# indor.net
KiCad netlist of a schematic drawn in EAGLE
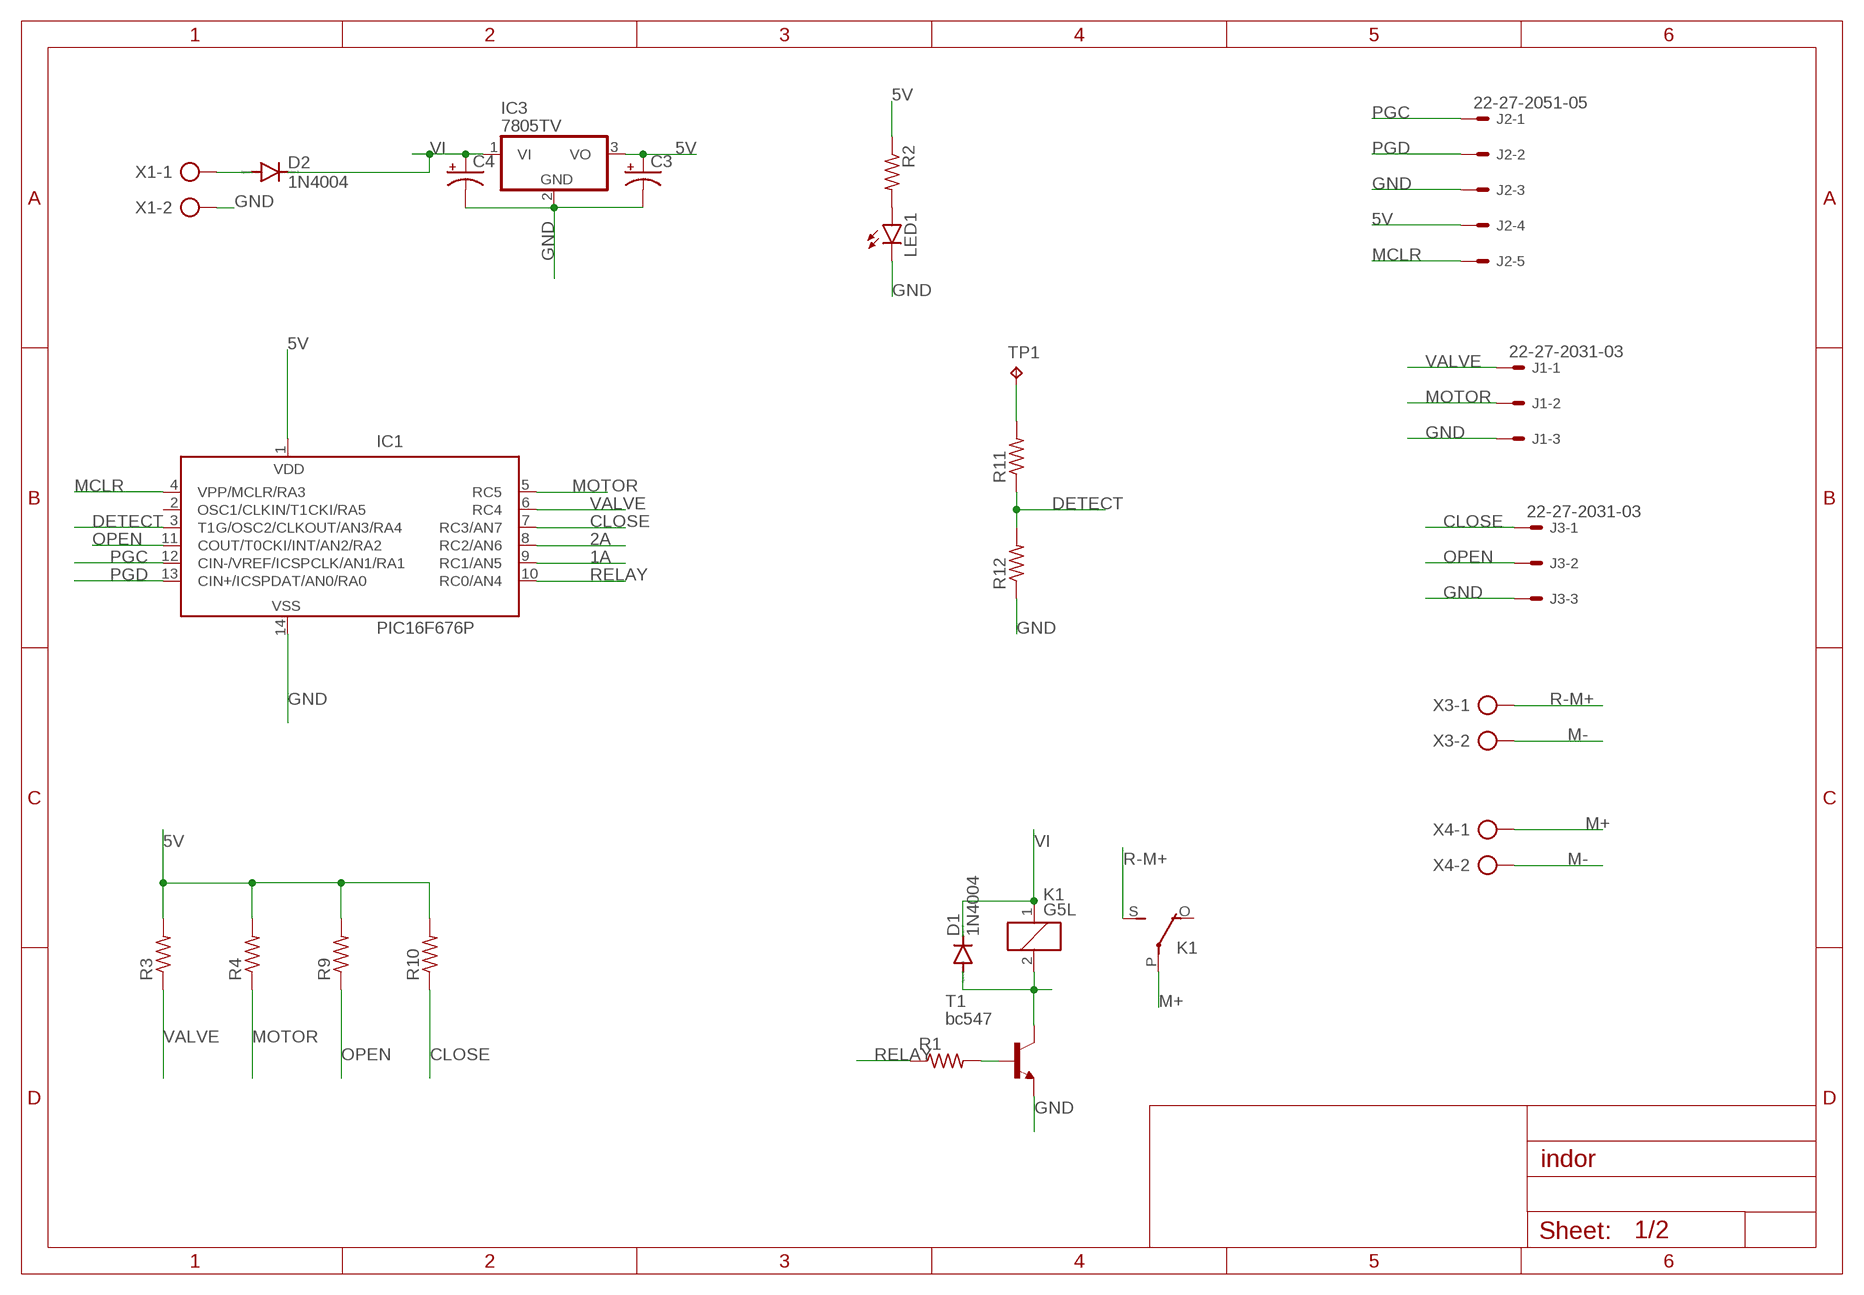
[diagram p0: schematic, sheet 1]
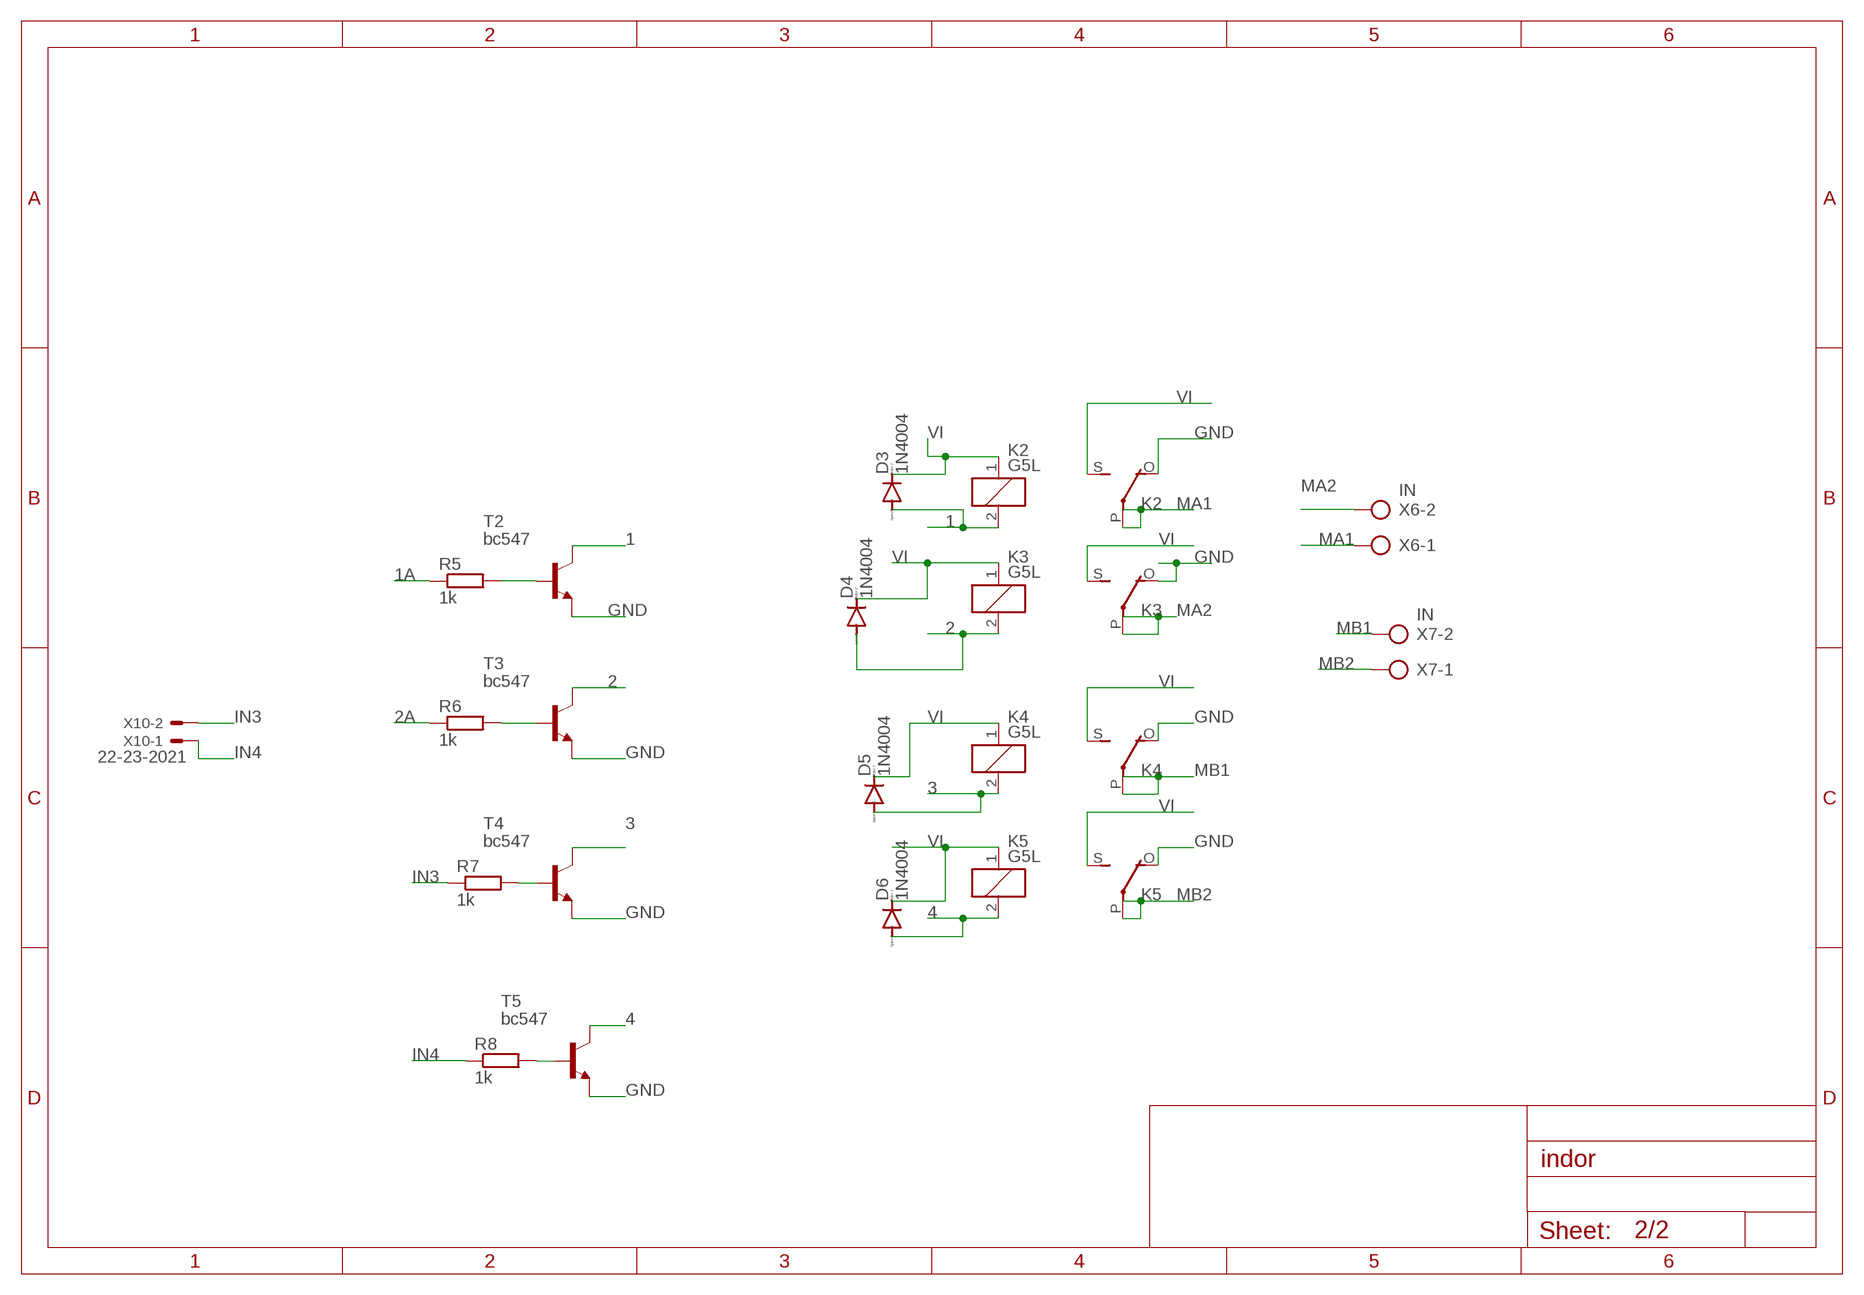
[diagram p1: schematic, sheet 2]

(export (version "E")
  (design (tool "Eeschema 10.0.6"))
  (components
    (comp (ref "C3")
      (value "CPOL-USE3.5-10")
      (footprint "eagle-import:E3,5-10")
      (libsource (lib "eagle-import") (part "CPOL-USE3.5-10"))
    )
    (comp (ref "C4")
      (value "CPOL-USE3.5-10")
      (footprint "eagle-import:E3,5-10")
      (libsource (lib "eagle-import") (part "CPOL-USE3.5-10"))
    )
    (comp (ref "D1")
      (value "1N4004")
      (footprint "eagle-import:DO41-10")
      (libsource (lib "eagle-import") (part "1N4004"))
    )
    (comp (ref "D2")
      (value "1N4004")
      (footprint "eagle-import:DO41-10")
      (libsource (lib "eagle-import") (part "1N4004"))
    )
    (comp (ref "IC1")
      (value "PIC16F676P")
      (footprint "eagle-import:DIL14")
      (fields (field (name "MF") "MICROCHIP") (field (name "MPN") "PIC16F676-I/P"))
      (libsource (lib "eagle-import") (part "PIC16F676P"))
    )
    (comp (ref "IC3")
      (value "7805TV")
      (footprint "eagle-import:TO220V")
      (libsource (lib "eagle-import") (part "78TV05"))
    )
    (comp (ref "J1")
      (value "22-27-2031-03")
      (footprint "eagle-import:6410-03")
      (fields (field (name "MF") "MOLEX"))
      (libsource (lib "eagle-import") (part "22-?-0327-2031"))
    )
    (comp (ref "J2")
      (value "22-27-2051-05")
      (footprint "eagle-import:6410-05")
      (fields (field (name "MF") "MOLEX"))
      (libsource (lib "eagle-import") (part "22-?-0527-2051"))
    )
    (comp (ref "J3")
      (value "22-27-2031-03")
      (footprint "eagle-import:6410-03")
      (fields (field (name "MF") "MOLEX"))
      (libsource (lib "eagle-import") (part "22-?-0327-2031"))
    )
    (comp (ref "K1")
      (value "G5L")
      (footprint "eagle-import:G5LE")
      (libsource (lib "eagle-import") (part "G5L"))
    )
    (comp (ref "LED1")
      (value "LED5MM")
      (footprint "eagle-import:LED5MM")
      (libsource (lib "eagle-import") (part "LED5MM"))
    )
    (comp (ref "R1")
      (value "R-US_0207/10")
      (footprint "eagle-import:0207_10")
      (libsource (lib "eagle-import") (part "R-US_0207/10"))
    )
    (comp (ref "R2")
      (value "R-US_0207/10")
      (footprint "eagle-import:0207_10")
      (libsource (lib "eagle-import") (part "R-US_0207/10"))
    )
    (comp (ref "R3")
      (value "R-US_0207/10")
      (footprint "eagle-import:0207_10")
      (libsource (lib "eagle-import") (part "R-US_0207/10"))
    )
    (comp (ref "R4")
      (value "R-US_0207/10")
      (footprint "eagle-import:0207_10")
      (libsource (lib "eagle-import") (part "R-US_0207/10"))
    )
    (comp (ref "R9")
      (value "R-US_0207/10")
      (footprint "eagle-import:0207_10")
      (libsource (lib "eagle-import") (part "R-US_0207/10"))
    )
    (comp (ref "R10")
      (value "R-US_0207/10")
      (footprint "eagle-import:0207_10")
      (libsource (lib "eagle-import") (part "R-US_0207/10"))
    )
    (comp (ref "R11")
      (value "R-US_0207/10")
      (footprint "eagle-import:0207_10")
      (libsource (lib "eagle-import") (part "R-US_0207/10"))
    )
    (comp (ref "R12")
      (value "R-US_0207/10")
      (footprint "eagle-import:0207_10")
      (libsource (lib "eagle-import") (part "R-US_0207/10"))
    )
    (comp (ref "T1")
      (value "bc547")
      (footprint "eagle-import:TO92-CBE")
      (libsource (lib "eagle-import") (part "-NPN-TO92-CBEBC547"))
    )
    (comp (ref "TP1")
      (value "TPPAD1-13Y")
      (footprint "eagle-import:P1-13Y")
      (libsource (lib "eagle-import") (part "TPPAD1-13Y"))
    )
    (comp (ref "X1")
      (value "AK500/2")
      (footprint "eagle-import:AK500_2")
      (libsource (lib "eagle-import") (part "AK500/2"))
    )
    (comp (ref "X3")
      (value "AK500/2")
      (footprint "eagle-import:AK500_2")
      (libsource (lib "eagle-import") (part "AK500/2"))
    )
    (comp (ref "X4")
      (value "AK500/2")
      (footprint "eagle-import:AK500_2")
      (libsource (lib "eagle-import") (part "AK500/2"))
    )
    (comp (ref "D3")
      (value "1N4004")
      (footprint "eagle-import:DO41-10")
      (libsource (lib "eagle-import") (part "1N4004"))
    )
    (comp (ref "D4")
      (value "1N4004")
      (footprint "eagle-import:DO41-10")
      (libsource (lib "eagle-import") (part "1N4004"))
    )
    (comp (ref "D5")
      (value "1N4004")
      (footprint "eagle-import:DO41-10")
      (libsource (lib "eagle-import") (part "1N4004"))
    )
    (comp (ref "D6")
      (value "1N4004")
      (footprint "eagle-import:DO41-10")
      (libsource (lib "eagle-import") (part "1N4004"))
    )
    (comp (ref "K2")
      (value "G5L")
      (footprint "eagle-import:G5LE")
      (libsource (lib "eagle-import") (part "G5L"))
    )
    (comp (ref "K3")
      (value "G5L")
      (footprint "eagle-import:G5LE")
      (libsource (lib "eagle-import") (part "G5L"))
    )
    (comp (ref "K4")
      (value "G5L")
      (footprint "eagle-import:G5LE")
      (libsource (lib "eagle-import") (part "G5L"))
    )
    (comp (ref "K5")
      (value "G5L")
      (footprint "eagle-import:G5LE")
      (libsource (lib "eagle-import") (part "G5L"))
    )
    (comp (ref "R5")
      (value "1k")
      (footprint "eagle-import:0207_10")
      (libsource (lib "eagle-import") (part "R-EU_0207/10"))
    )
    (comp (ref "R6")
      (value "1k")
      (footprint "eagle-import:0207_10")
      (libsource (lib "eagle-import") (part "R-EU_0207/10"))
    )
    (comp (ref "R7")
      (value "1k")
      (footprint "eagle-import:0207_10")
      (libsource (lib "eagle-import") (part "R-EU_0207/10"))
    )
    (comp (ref "R8")
      (value "1k")
      (footprint "eagle-import:0207_10")
      (libsource (lib "eagle-import") (part "R-EU_0207/10"))
    )
    (comp (ref "T2")
      (value "bc547")
      (footprint "eagle-import:TO92-CBE")
      (libsource (lib "eagle-import") (part "-NPN-TO92-CBEBC547"))
    )
    (comp (ref "T3")
      (value "bc547")
      (footprint "eagle-import:TO92-CBE")
      (libsource (lib "eagle-import") (part "-NPN-TO92-CBEBC547"))
    )
    (comp (ref "T4")
      (value "bc547")
      (footprint "eagle-import:TO92-CBE")
      (libsource (lib "eagle-import") (part "-NPN-TO92-CBEBC547"))
    )
    (comp (ref "T5")
      (value "bc547")
      (footprint "eagle-import:TO92-CBE")
      (libsource (lib "eagle-import") (part "-NPN-TO92-CBEBC547"))
    )
    (comp (ref "X6")
      (value "IN")
      (footprint "eagle-import:AK500_2")
      (libsource (lib "eagle-import") (part "AK500/2"))
    )
    (comp (ref "X7")
      (value "IN")
      (footprint "eagle-import:AK500_2")
      (libsource (lib "eagle-import") (part "AK500/2"))
    )
    (comp (ref "X10")
      (value "22-23-2021")
      (footprint "eagle-import:22-23-2021")
      (fields (field (name "MF") "MOLEX"))
      (libsource (lib "eagle-import") (part "22-23-2021"))
    )
  )
  (nets
    (net (code "1") (name "1") (class "Default")
      (node (ref "D3") (pin "A") (pinfunction "A_A") (pintype "passive"))
      (node (ref "K2") (pin "2") (pinfunction "2_2") (pintype "passive"))
      (node (ref "T2") (pin "C") (pinfunction "C_C") (pintype "passive"))
    )
    (net (code "2") (name "1A") (class "Default")
      (node (ref "IC1") (pin "9") (pinfunction "RC1/AN5_9") (pintype "bidirectional"))
      (node (ref "R5") (pin "1") (pinfunction "1_1") (pintype "passive"))
    )
    (net (code "3") (name "2") (class "Default")
      (node (ref "D4") (pin "A") (pinfunction "A_A") (pintype "passive"))
      (node (ref "K3") (pin "2") (pinfunction "2_2") (pintype "passive"))
      (node (ref "T3") (pin "C") (pinfunction "C_C") (pintype "passive"))
    )
    (net (code "4") (name "2A") (class "Default")
      (node (ref "IC1") (pin "8") (pinfunction "RC2/AN6_8") (pintype "bidirectional"))
      (node (ref "R6") (pin "1") (pinfunction "1_1") (pintype "passive"))
    )
    (net (code "5") (name "3") (class "Default")
      (node (ref "D5") (pin "A") (pinfunction "A_A") (pintype "passive"))
      (node (ref "K4") (pin "2") (pinfunction "2_2") (pintype "passive"))
      (node (ref "T4") (pin "C") (pinfunction "C_C") (pintype "passive"))
    )
    (net (code "6") (name "4") (class "Default")
      (node (ref "D6") (pin "A") (pinfunction "A_A") (pintype "passive"))
      (node (ref "K5") (pin "2") (pinfunction "2_2") (pintype "passive"))
      (node (ref "T5") (pin "C") (pinfunction "C_C") (pintype "passive"))
    )
    (net (code "7") (name "5V") (class "Default")
      (node (ref "C3") (pin "+") (pinfunction "+_+") (pintype "passive"))
      (node (ref "IC1") (pin "1") (pinfunction "VDD_1") (pintype "power_in"))
      (node (ref "IC3") (pin "3") (pinfunction "VO_3") (pintype "passive"))
      (node (ref "J2") (pin "4") (pinfunction "S_4") (pintype "passive"))
      (node (ref "R10") (pin "2") (pinfunction "2_2") (pintype "passive"))
      (node (ref "R2") (pin "1") (pinfunction "1_1") (pintype "passive"))
      (node (ref "R3") (pin "2") (pinfunction "2_2") (pintype "passive"))
      (node (ref "R4") (pin "2") (pinfunction "2_2") (pintype "passive"))
      (node (ref "R9") (pin "2") (pinfunction "2_2") (pintype "passive"))
    )
    (net (code "8") (name "CLOSE") (class "Default")
      (node (ref "IC1") (pin "7") (pinfunction "RC3/AN7_7") (pintype "bidirectional"))
      (node (ref "J3") (pin "1") (pinfunction "S_1") (pintype "passive"))
      (node (ref "R10") (pin "1") (pinfunction "1_1") (pintype "passive"))
    )
    (net (code "9") (name "DETECT") (class "Default")
      (node (ref "IC1") (pin "3") (pinfunction "T1G/OSC2/CLKOUT/AN3/RA4_3") (pintype "bidirectional"))
      (node (ref "R11") (pin "1") (pinfunction "1_1") (pintype "passive"))
      (node (ref "R12") (pin "2") (pinfunction "2_2") (pintype "passive"))
    )
    (net (code "10") (name "GND") (class "Default")
      (node (ref "C3") (pin "-") (pinfunction "-_-") (pintype "passive"))
      (node (ref "C4") (pin "-") (pinfunction "-_-") (pintype "passive"))
      (node (ref "IC1") (pin "14") (pinfunction "VSS_14") (pintype "power_in"))
      (node (ref "IC3") (pin "2") (pinfunction "GND_2") (pintype "passive"))
      (node (ref "J1") (pin "3") (pinfunction "S_3") (pintype "passive"))
      (node (ref "J2") (pin "3") (pinfunction "S_3") (pintype "passive"))
      (node (ref "J3") (pin "3") (pinfunction "S_3") (pintype "passive"))
      (node (ref "K2") (pin "O") (pinfunction "O_O") (pintype "passive"))
      (node (ref "K3") (pin "O") (pinfunction "O_O") (pintype "passive"))
      (node (ref "K4") (pin "O") (pinfunction "O_O") (pintype "passive"))
      (node (ref "K5") (pin "O") (pinfunction "O_O") (pintype "passive"))
      (node (ref "LED1") (pin "K") (pinfunction "C_K") (pintype "passive"))
      (node (ref "R12") (pin "1") (pinfunction "1_1") (pintype "passive"))
      (node (ref "T1") (pin "E") (pinfunction "E_E") (pintype "passive"))
      (node (ref "T2") (pin "E") (pinfunction "E_E") (pintype "passive"))
      (node (ref "T3") (pin "E") (pinfunction "E_E") (pintype "passive"))
      (node (ref "T4") (pin "E") (pinfunction "E_E") (pintype "passive"))
      (node (ref "T5") (pin "E") (pinfunction "E_E") (pintype "passive"))
      (node (ref "X1") (pin "2") (pinfunction "KL_2") (pintype "passive"))
    )
    (net (code "11") (name "IN3") (class "Default")
      (node (ref "R7") (pin "1") (pinfunction "1_1") (pintype "passive"))
      (node (ref "X10") (pin "2") (pinfunction "S_2") (pintype "passive"))
    )
    (net (code "12") (name "IN4") (class "Default")
      (node (ref "R8") (pin "1") (pinfunction "1_1") (pintype "passive"))
      (node (ref "X10") (pin "1") (pinfunction "S_1") (pintype "passive"))
    )
    (net (code "13") (name "M+") (class "Default")
      (node (ref "K1") (pin "P") (pinfunction "P_P") (pintype "passive"))
      (node (ref "X4") (pin "1") (pinfunction "KL_1") (pintype "passive"))
    )
    (net (code "14") (name "M-") (class "Default")
      (node (ref "X3") (pin "2") (pinfunction "KL_2") (pintype "passive"))
      (node (ref "X4") (pin "2") (pinfunction "KL_2") (pintype "passive"))
    )
    (net (code "15") (name "MA1") (class "Default")
      (node (ref "K2") (pin "P") (pinfunction "P_P") (pintype "passive"))
      (node (ref "X6") (pin "1") (pinfunction "KL_1") (pintype "passive"))
    )
    (net (code "16") (name "MA2") (class "Default")
      (node (ref "K3") (pin "P") (pinfunction "P_P") (pintype "passive"))
      (node (ref "X6") (pin "2") (pinfunction "KL_2") (pintype "passive"))
    )
    (net (code "17") (name "MB1") (class "Default")
      (node (ref "K4") (pin "P") (pinfunction "P_P") (pintype "passive"))
      (node (ref "X7") (pin "2") (pinfunction "KL_2") (pintype "passive"))
    )
    (net (code "18") (name "MB2") (class "Default")
      (node (ref "K5") (pin "P") (pinfunction "P_P") (pintype "passive"))
      (node (ref "X7") (pin "1") (pinfunction "KL_1") (pintype "passive"))
    )
    (net (code "19") (name "MCLR") (class "Default")
      (node (ref "IC1") (pin "4") (pinfunction "VPP/MCLR/RA3_4") (pintype "input"))
      (node (ref "J2") (pin "5") (pinfunction "S_5") (pintype "passive"))
    )
    (net (code "20") (name "MOTOR") (class "Default")
      (node (ref "IC1") (pin "5") (pinfunction "RC5_5") (pintype "bidirectional"))
      (node (ref "J1") (pin "2") (pinfunction "S_2") (pintype "passive"))
      (node (ref "R4") (pin "1") (pinfunction "1_1") (pintype "passive"))
    )
    (net (code "21") (name "Net-(D1-PadA)") (class "Default")
      (node (ref "D1") (pin "A") (pinfunction "A_A") (pintype "passive"))
      (node (ref "K1") (pin "2") (pinfunction "2_2") (pintype "passive"))
      (node (ref "T1") (pin "C") (pinfunction "C_C") (pintype "passive"))
    )
    (net (code "22") (name "Net-(LED1-PadA)") (class "Default")
      (node (ref "LED1") (pin "A") (pinfunction "A_A") (pintype "passive"))
      (node (ref "R2") (pin "2") (pinfunction "2_2") (pintype "passive"))
    )
    (net (code "23") (name "Net-(R1-Pad2)") (class "Default")
      (node (ref "R1") (pin "2") (pinfunction "2_2") (pintype "passive"))
      (node (ref "T1") (pin "B") (pinfunction "B_B") (pintype "passive"))
    )
    (net (code "24") (name "Net-(R5-Pad2)") (class "Default")
      (node (ref "R5") (pin "2") (pinfunction "2_2") (pintype "passive"))
      (node (ref "T2") (pin "B") (pinfunction "B_B") (pintype "passive"))
    )
    (net (code "25") (name "Net-(R6-Pad2)") (class "Default")
      (node (ref "R6") (pin "2") (pinfunction "2_2") (pintype "passive"))
      (node (ref "T3") (pin "B") (pinfunction "B_B") (pintype "passive"))
    )
    (net (code "26") (name "Net-(R7-Pad2)") (class "Default")
      (node (ref "R7") (pin "2") (pinfunction "2_2") (pintype "passive"))
      (node (ref "T4") (pin "B") (pinfunction "B_B") (pintype "passive"))
    )
    (net (code "27") (name "Net-(R8-Pad2)") (class "Default")
      (node (ref "R8") (pin "2") (pinfunction "2_2") (pintype "passive"))
      (node (ref "T5") (pin "B") (pinfunction "B_B") (pintype "passive"))
    )
    (net (code "28") (name "Net-(R11-Pad2)") (class "Default")
      (node (ref "R11") (pin "2") (pinfunction "2_2") (pintype "passive"))
      (node (ref "TP1") (pin "TP") (pinfunction "TP_TP") (pintype "input"))
    )
    (net (code "29") (name "Net-(X1A-KL)") (class "Default")
      (node (ref "D2") (pin "A") (pinfunction "A_A") (pintype "passive"))
      (node (ref "X1") (pin "1") (pinfunction "KL_1") (pintype "passive"))
    )
    (net (code "30") (name "OPEN") (class "Default")
      (node (ref "IC1") (pin "11") (pinfunction "COUT/T0CKI/INT/AN2/RA2_11") (pintype "bidirectional"))
      (node (ref "J3") (pin "2") (pinfunction "S_2") (pintype "passive"))
      (node (ref "R9") (pin "1") (pinfunction "1_1") (pintype "passive"))
    )
    (net (code "31") (name "PGC") (class "Default")
      (node (ref "IC1") (pin "12") (pinfunction "CIN-/VREF/ICSPCLK/AN1/RA1_12") (pintype "bidirectional"))
      (node (ref "J2") (pin "1") (pinfunction "S_1") (pintype "passive"))
    )
    (net (code "32") (name "PGD") (class "Default")
      (node (ref "IC1") (pin "13") (pinfunction "CIN+/ICSPDAT/AN0/RA0_13") (pintype "bidirectional"))
      (node (ref "J2") (pin "2") (pinfunction "S_2") (pintype "passive"))
    )
    (net (code "33") (name "R-M+") (class "Default")
      (node (ref "K1") (pin "S") (pinfunction "S_S") (pintype "passive"))
      (node (ref "X3") (pin "1") (pinfunction "KL_1") (pintype "passive"))
    )
    (net (code "34") (name "RELAY") (class "Default")
      (node (ref "IC1") (pin "10") (pinfunction "RC0/AN4_10") (pintype "bidirectional"))
      (node (ref "R1") (pin "1") (pinfunction "1_1") (pintype "passive"))
    )
    (net (code "35") (name "VALVE") (class "Default")
      (node (ref "IC1") (pin "6") (pinfunction "RC4_6") (pintype "bidirectional"))
      (node (ref "J1") (pin "1") (pinfunction "S_1") (pintype "passive"))
      (node (ref "R3") (pin "1") (pinfunction "1_1") (pintype "passive"))
    )
    (net (code "36") (name "VI") (class "Default")
      (node (ref "C4") (pin "+") (pinfunction "+_+") (pintype "passive"))
      (node (ref "D1") (pin "C") (pinfunction "C_C") (pintype "passive"))
      (node (ref "D2") (pin "C") (pinfunction "C_C") (pintype "passive"))
      (node (ref "D3") (pin "C") (pinfunction "C_C") (pintype "passive"))
      (node (ref "D4") (pin "C") (pinfunction "C_C") (pintype "passive"))
      (node (ref "D5") (pin "C") (pinfunction "C_C") (pintype "passive"))
      (node (ref "D6") (pin "C") (pinfunction "C_C") (pintype "passive"))
      (node (ref "IC3") (pin "1") (pinfunction "VI_1") (pintype "input"))
      (node (ref "K1") (pin "1") (pinfunction "1_1") (pintype "passive"))
      (node (ref "K2") (pin "1") (pinfunction "1_1") (pintype "passive"))
      (node (ref "K2") (pin "S") (pinfunction "S_S") (pintype "passive"))
      (node (ref "K3") (pin "1") (pinfunction "1_1") (pintype "passive"))
      (node (ref "K3") (pin "S") (pinfunction "S_S") (pintype "passive"))
      (node (ref "K4") (pin "1") (pinfunction "1_1") (pintype "passive"))
      (node (ref "K4") (pin "S") (pinfunction "S_S") (pintype "passive"))
      (node (ref "K5") (pin "1") (pinfunction "1_1") (pintype "passive"))
      (node (ref "K5") (pin "S") (pinfunction "S_S") (pintype "passive"))
    )
    (net (code "37") (name "unconnected-(IC1-OSC1{slash}CLKIN{slash}T1CKI{slash}RA5-Pad2)") (class "Default")
      (node (ref "IC1") (pin "2") (pinfunction "OSC1/CLKIN/T1CKI/RA5_2") (pintype "bidirectional"))
    )
    (net (code "38") (name "unconnected-(K1-PadO)") (class "Default")
      (node (ref "K1") (pin "O") (pinfunction "O_O") (pintype "passive"))
    )
  )
)
